# broadcast.net
KiCad netlist of a schematic drawn in Altium Designer
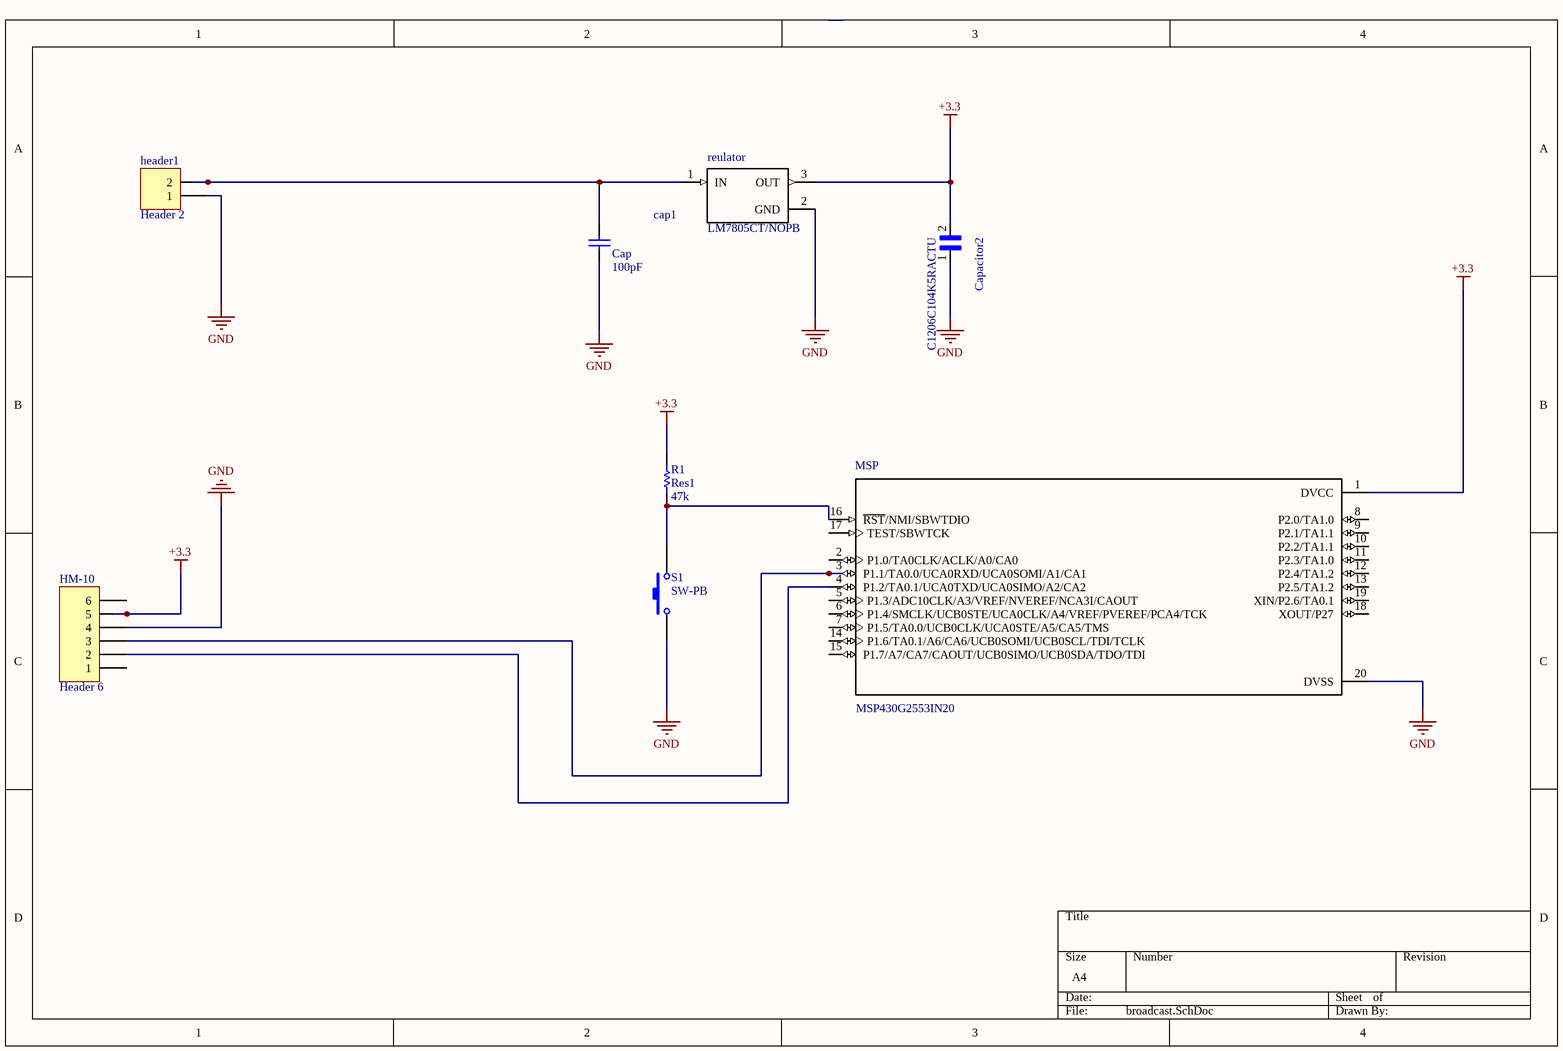
[diagram p0: broadcast.SchDoc]

(export (version "E")
  (design (tool "Eeschema 10.0.6"))
  (components
    (comp (ref "cap1")
      (value "Cap")
      (footprint "RAD-0.3")
      (description "Capacitor")
      (fields (field (name "ALTIUM_VALUE") "100pF") (field (name "PUBLISHER") "Altium Limited"))
      (libsource (lib "Miscellaneous Devices") (part "Cap"))
    )
    (comp (ref "Capacitor2")
      (value "C1206C104K5RACTU")
      (footprint "*VARC3216X85N")
      (fields (field (name "MF") "KEMET"))
      (libsource (lib "C1206C104K5RACTU") (part "C1206C104K5RACTU"))
    )
    (comp (ref "header1")
      (value "Header 2")
      (footprint "HDR1X2")
      (description "Header, 2-Pin")
      (fields (field (name "PUBLISHER") "Altium Limited"))
      (libsource (lib "Miscellaneous Connectors") (part "Header 2"))
    )
    (comp (ref "HM-10")
      (value "Header 6")
      (footprint "HDR1X6")
      (description "Header, 6-Pin")
      (fields (field (name "PUBLISHER") "Altium Limited"))
      (libsource (lib "Miscellaneous Connectors") (part "Header 6"))
    )
    (comp (ref "MSP")
      (value "MSP430G2553IN20")
      (footprint "*DIP794W45P254L2692H508Q20")
      (description "MSP430G2x53, MSP430G2x13 Mixed Signal Microcontroller 20-PDIP -40 to 85")
      (fields (field (name "MF") "Texas Instruments"))
      (libsource (lib "MSP430G2553IN20") (part "MSP430G2553IN20"))
    )
    (comp (ref "R1")
      (value "Res1")
      (footprint "AXIAL-0.3")
      (description "Resistor")
      (fields (field (name "ALTIUM_VALUE") "47k") (field (name "PUBLISHER") "Altium Limited"))
      (libsource (lib "Miscellaneous Devices") (part "Res1"))
    )
    (comp (ref "reulator")
      (value "LM7805CT/NOPB")
      (footprint "*TO254P1054X470X2600-3")
      (description "IC REG DOÄRUSAL 5V 1A TO220AB")
      (fields (field (name "MF") "ON Semiconductor") (field (name "MP") "LM7805CT"))
      (libsource (lib "LM7805CT_NOPB") (part "LM7805CT/NOPB"))
    )
    (comp (ref "S1")
      (value "SW-PB")
      (footprint "SPST-2")
      (description "Switch")
      (fields (field (name "PUBLISHER") "Altium Limited"))
      (libsource (lib "Miscellaneous Devices") (part "SW-PB"))
    )
  )
  (nets
    (net (code "1") (name "+3.3") (class "Default")
      (node (ref "Capacitor2") (pin "2") (pinfunction "2_2") (pintype "passive"))
      (node (ref "HM-10") (pin "5") (pinfunction "5_5") (pintype "passive"))
      (node (ref "MSP") (pin "1") (pinfunction "DVCC_1") (pintype "power_in"))
      (node (ref "R1") (pin "2") (pinfunction "2_2") (pintype "passive"))
      (node (ref "reulator") (pin "3") (pinfunction "OUT_3") (pintype "output"))
    )
    (net (code "2") (name "GND") (class "Default")
      (node (ref "Capacitor2") (pin "1") (pinfunction "1_1") (pintype "passive"))
      (node (ref "HM-10") (pin "4") (pinfunction "4_4") (pintype "passive"))
      (node (ref "MSP") (pin "20") (pinfunction "DVSS_20") (pintype "power_in"))
      (node (ref "S1") (pin "1") (pinfunction "1_1") (pintype "passive"))
      (node (ref "cap1") (pin "1") (pinfunction "1_1") (pintype "passive"))
      (node (ref "header1") (pin "1") (pinfunction "1_1") (pintype "passive"))
      (node (ref "reulator") (pin "2") (pinfunction "GND_2") (pintype "power_in"))
    )
    (net (code "3") (name "Net-(MSP-P1.1{slash}TA0.0{slash}UCA0RXD{slash}UCA0SOMI{slash}A1{slash}CA1)") (class "Default")
      (node (ref "HM-10") (pin "3") (pinfunction "3_3") (pintype "passive"))
      (node (ref "MSP") (pin "3") (pinfunction "P1.1/TA0.0/UCA0RXD/UCA0SOMI/A1/CA1_3") (pintype "bidirectional"))
    )
    (net (code "4") (name "Net-(MSP-P1.2{slash}TA0.1{slash}UCA0TXD{slash}UCA0SIMO{slash}A2{slash}CA2)") (class "Default")
      (node (ref "HM-10") (pin "2") (pinfunction "2_2") (pintype "passive"))
      (node (ref "MSP") (pin "4") (pinfunction "P1.2/TA0.1/UCA0TXD/UCA0SIMO/A2/CA2_4") (pintype "bidirectional"))
    )
    (net (code "5") (name "Net-(MSP-~{RST}{slash}NMI{slash}SBWTDIO)") (class "Default")
      (node (ref "MSP") (pin "16") (pinfunction "~{RST}/NMI/SBWTDIO_16") (pintype "input"))
      (node (ref "R1") (pin "1") (pinfunction "1_1") (pintype "passive"))
      (node (ref "S1") (pin "2") (pinfunction "2_2") (pintype "passive"))
    )
    (net (code "6") (name "Net-(reulator-IN)") (class "Default")
      (node (ref "cap1") (pin "2") (pinfunction "2_2") (pintype "passive"))
      (node (ref "header1") (pin "2") (pinfunction "2_2") (pintype "passive"))
      (node (ref "reulator") (pin "1") (pinfunction "IN_1") (pintype "input"))
    )
    (net (code "7") (name "unconnected-(HM-10-Pad1)") (class "Default")
      (node (ref "HM-10") (pin "1") (pinfunction "1_1") (pintype "passive"))
    )
    (net (code "8") (name "unconnected-(HM-10-Pad6)") (class "Default")
      (node (ref "HM-10") (pin "6") (pinfunction "6_6") (pintype "passive"))
    )
    (net (code "9") (name "unconnected-(MSP-P1.0{slash}TA0CLK{slash}ACLK{slash}A0{slash}CA0-Pad2)") (class "Default")
      (node (ref "MSP") (pin "2") (pinfunction "P1.0/TA0CLK/ACLK/A0/CA0_2") (pintype "bidirectional"))
    )
    (net (code "10") (name "unconnected-(MSP-P1.3{slash}ADC10CLK{slash}A3{slash}VREF{slash}NVEREF{slash}NCA3I{slash}CAOUT-Pad5)") (class "Default")
      (node (ref "MSP") (pin "5") (pinfunction "P1.3/ADC10CLK/A3/VREF/NVEREF/NCA3I/CAOUT_5") (pintype "bidirectional"))
    )
    (net (code "11") (name "unconnected-(MSP-P1.4{slash}SMCLK{slash}UCB0STE{slash}UCA0CLK{slash}A4{slash}VREF{slash}PVEREF{slash}PCA4{slash}TCK-Pad6)") (class "Default")
      (node (ref "MSP") (pin "6") (pinfunction "P1.4/SMCLK/UCB0STE/UCA0CLK/A4/VREF/PVEREF/PCA4/TCK_6") (pintype "bidirectional"))
    )
    (net (code "12") (name "unconnected-(MSP-P1.5{slash}TA0.0{slash}UCB0CLK{slash}UCA0STE{slash}A5{slash}CA5{slash}TMS-Pad7)") (class "Default")
      (node (ref "MSP") (pin "7") (pinfunction "P1.5/TA0.0/UCB0CLK/UCA0STE/A5/CA5/TMS_7") (pintype "bidirectional"))
    )
    (net (code "13") (name "unconnected-(MSP-P1.6{slash}TA0.1{slash}A6{slash}CA6{slash}UCB0SOMI{slash}UCB0SCL{slash}TDI{slash}TCLK-Pad14)") (class "Default")
      (node (ref "MSP") (pin "14") (pinfunction "P1.6/TA0.1/A6/CA6/UCB0SOMI/UCB0SCL/TDI/TCLK_14") (pintype "bidirectional"))
    )
    (net (code "14") (name "unconnected-(MSP-P1.7{slash}A7{slash}CA7{slash}CAOUT{slash}UCB0SIMO{slash}UCB0SDA{slash}TDO{slash}TDI-Pad15)") (class "Default")
      (node (ref "MSP") (pin "15") (pinfunction "P1.7/A7/CA7/CAOUT/UCB0SIMO/UCB0SDA/TDO/TDI_15") (pintype "bidirectional"))
    )
    (net (code "15") (name "unconnected-(MSP-P2.0{slash}TA1.0-Pad8)") (class "Default")
      (node (ref "MSP") (pin "8") (pinfunction "P2.0/TA1.0_8") (pintype "bidirectional"))
    )
    (net (code "16") (name "unconnected-(MSP-P2.1{slash}TA1.1-Pad9)") (class "Default")
      (node (ref "MSP") (pin "9") (pinfunction "P2.1/TA1.1_9") (pintype "bidirectional"))
    )
    (net (code "17") (name "unconnected-(MSP-P2.2{slash}TA1.1-Pad10)") (class "Default")
      (node (ref "MSP") (pin "10") (pinfunction "P2.2/TA1.1_10") (pintype "bidirectional"))
    )
    (net (code "18") (name "unconnected-(MSP-P2.3{slash}TA1.0-Pad11)") (class "Default")
      (node (ref "MSP") (pin "11") (pinfunction "P2.3/TA1.0_11") (pintype "bidirectional"))
    )
    (net (code "19") (name "unconnected-(MSP-P2.4{slash}TA1.2-Pad12)") (class "Default")
      (node (ref "MSP") (pin "12") (pinfunction "P2.4/TA1.2_12") (pintype "bidirectional"))
    )
    (net (code "20") (name "unconnected-(MSP-P2.5{slash}TA1.2-Pad13)") (class "Default")
      (node (ref "MSP") (pin "13") (pinfunction "P2.5/TA1.2_13") (pintype "bidirectional"))
    )
    (net (code "21") (name "unconnected-(MSP-TEST{slash}SBWTCK-Pad17)") (class "Default")
      (node (ref "MSP") (pin "17") (pinfunction "TEST/SBWTCK_17") (pintype "input"))
    )
    (net (code "22") (name "unconnected-(MSP-XIN{slash}P2.6{slash}TA0.1-Pad19)") (class "Default")
      (node (ref "MSP") (pin "19") (pinfunction "XIN/P2.6/TA0.1_19") (pintype "bidirectional"))
    )
    (net (code "23") (name "unconnected-(MSP-XOUT{slash}P27-Pad18)") (class "Default")
      (node (ref "MSP") (pin "18") (pinfunction "XOUT/P27_18") (pintype "bidirectional"))
    )
  )
)
